# 13_-_USB.net
KiCad netlist of a schematic drawn in Altium Designer
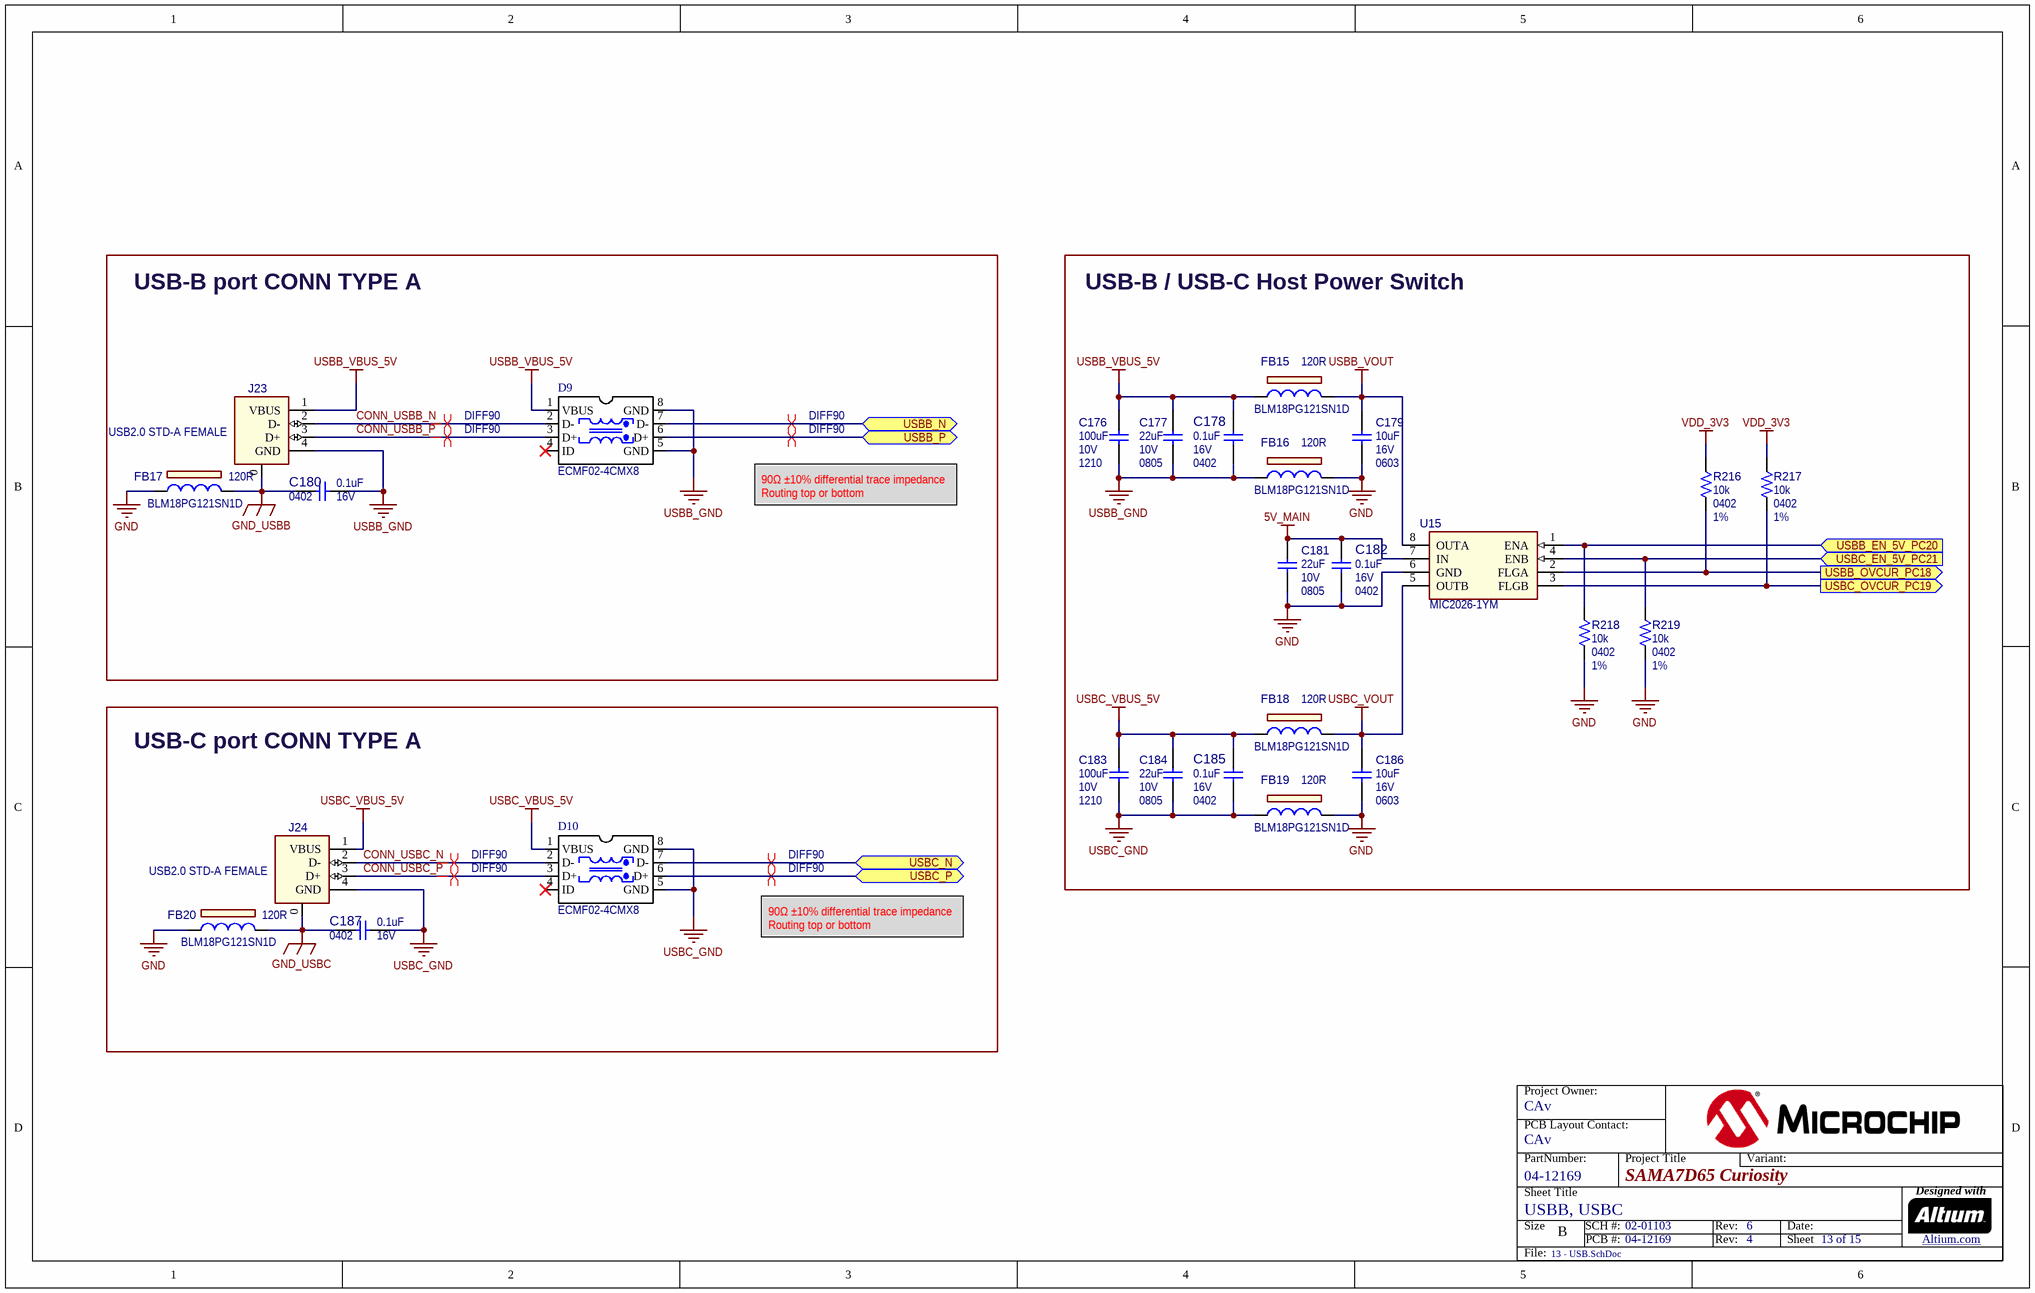
[diagram p0: 13 - USB.SchDoc]

(export (version "E")
  (design (tool "Eeschema 10.0.6"))
  (components
    (comp (ref "C176")
      (value "100uF")
      (footprint "CAP_C_1210")
      (description "Capacitor")
      (fields
        (field (name "VOLTAGE") "10V")
        (field (name "PACKAGE") "1210")
        (field (name "TOLERANCE") "20%")
        (field (name "Comment") "Capacitor NP")
      )
      (libsource (lib "") (part "Capacitor NP_1"))
    )
    (comp (ref "C177")
      (value "22uF")
      (footprint "CAP_C_0805")
      (fields
        (field (name "VOLTAGE") "10V")
        (field (name "PACKAGE") "0805")
        (field (name "TOLERANCE") "20%")
        (field (name "Comment") "Capacitor NP")
        (field (name "OWNER") "Razvan Cristescu")
      )
      (libsource (lib "MCHP-CDB") (part "Capacitor NP"))
    )
    (comp (ref "C178")
      (value "0.1uF")
      (footprint "CAP_C_0402")
      (fields
        (field (name "VOLTAGE") "16V")
        (field (name "PACKAGE") "0402")
        (field (name "TOLERANCE") "10%")
        (field (name "Comment") "Capacitor NP")
        (field (name "OWNER") "Sompoch Loboonlert")
      )
      (libsource (lib "MCHP-CDB") (part "Capacitor NP"))
    )
    (comp (ref "C179")
      (value "10uF")
      (footprint "CAP_C_0603")
      (fields
        (field (name "VOLTAGE") "16V")
        (field (name "PACKAGE") "0603")
        (field (name "TOLERANCE") "10%")
        (field (name "Comment") "Capacitor NP")
        (field (name "OWNER") "Sam Charles")
      )
      (libsource (lib "MCHP-CDB") (part "Capacitor NP"))
    )
    (comp (ref "C180")
      (value "0.1uF")
      (footprint "CAP_C_0402")
      (fields
        (field (name "VOLTAGE") "16V")
        (field (name "PACKAGE") "0402")
        (field (name "TOLERANCE") "10%")
        (field (name "Comment") "Capacitor NP")
        (field (name "OWNER") "Sompoch Loboonlert")
      )
      (libsource (lib "MCHP-CDB") (part "Capacitor NP"))
    )
    (comp (ref "C181")
      (value "22uF")
      (footprint "CAP_C_0805")
      (fields
        (field (name "VOLTAGE") "10V")
        (field (name "PACKAGE") "0805")
        (field (name "TOLERANCE") "20%")
        (field (name "Comment") "Capacitor NP")
        (field (name "OWNER") "Razvan Cristescu")
      )
      (libsource (lib "MCHP-CDB") (part "Capacitor NP"))
    )
    (comp (ref "C182")
      (value "0.1uF")
      (footprint "CAP_C_0402")
      (fields
        (field (name "VOLTAGE") "16V")
        (field (name "PACKAGE") "0402")
        (field (name "TOLERANCE") "10%")
        (field (name "Comment") "Capacitor NP")
        (field (name "OWNER") "Sompoch Loboonlert")
      )
      (libsource (lib "MCHP-CDB") (part "Capacitor NP"))
    )
    (comp (ref "C183")
      (value "100uF")
      (footprint "CAP_C_1210")
      (description "Capacitor")
      (fields
        (field (name "VOLTAGE") "10V")
        (field (name "PACKAGE") "1210")
        (field (name "TOLERANCE") "20%")
        (field (name "Comment") "Capacitor NP")
      )
      (libsource (lib "") (part "Capacitor NP_1"))
    )
    (comp (ref "C184")
      (value "22uF")
      (footprint "CAP_C_0805")
      (fields
        (field (name "VOLTAGE") "10V")
        (field (name "PACKAGE") "0805")
        (field (name "TOLERANCE") "20%")
        (field (name "Comment") "Capacitor NP")
        (field (name "OWNER") "Razvan Cristescu")
      )
      (libsource (lib "MCHP-CDB") (part "Capacitor NP"))
    )
    (comp (ref "C185")
      (value "0.1uF")
      (footprint "CAP_C_0402")
      (fields
        (field (name "VOLTAGE") "16V")
        (field (name "PACKAGE") "0402")
        (field (name "TOLERANCE") "10%")
        (field (name "Comment") "Capacitor NP")
        (field (name "OWNER") "Sompoch Loboonlert")
      )
      (libsource (lib "MCHP-CDB") (part "Capacitor NP"))
    )
    (comp (ref "C186")
      (value "10uF")
      (footprint "CAP_C_0603")
      (fields
        (field (name "VOLTAGE") "16V")
        (field (name "PACKAGE") "0603")
        (field (name "TOLERANCE") "10%")
        (field (name "Comment") "Capacitor NP")
        (field (name "OWNER") "Sam Charles")
      )
      (libsource (lib "MCHP-CDB") (part "Capacitor NP"))
    )
    (comp (ref "C187")
      (value "0.1uF")
      (footprint "CAP_C_0402")
      (fields
        (field (name "VOLTAGE") "16V")
        (field (name "PACKAGE") "0402")
        (field (name "TOLERANCE") "10%")
        (field (name "Comment") "Capacitor NP")
        (field (name "OWNER") "Sompoch Loboonlert")
      )
      (libsource (lib "MCHP-CDB") (part "Capacitor NP"))
    )
    (comp (ref "D9")
      (value "ECMF02-4CMX8")
      (footprint "DIODE ESD ECMF02-4CMX8")
      (description "IC ESD FILTER COMM MODE 8-UQFN")
      (fields (field (name "Comment") "ESD_ECMF02-4CMX8") (field (name "OWNER") "Dragos Danaila"))
      (libsource (lib "MCHP-CDB") (part "DIODE ESD ECMF02-4CMX8"))
    )
    (comp (ref "D10")
      (value "ECMF02-4CMX8")
      (footprint "DIODE ESD ECMF02-4CMX8")
      (description "IC ESD FILTER COMM MODE 8-UQFN")
      (fields (field (name "Comment") "ESD_ECMF02-4CMX8") (field (name "OWNER") "Dragos Danaila"))
      (libsource (lib "MCHP-CDB") (part "DIODE ESD ECMF02-4CMX8"))
    )
    (comp (ref "FB15")
      (value "120R")
      (footprint "IND_C_0603")
      (fields
        (field (name "MANUFACTURER PART NUMBER 1") "BLM18PG121SN1D")
        (field (name "Comment") "Ferrite Bead")
        (field (name "OWNER") "Petnarong Chaijaroong")
      )
      (libsource (lib "MCHP-CDB") (part "Ferrite Bead"))
    )
    (comp (ref "FB16")
      (value "120R")
      (footprint "IND_C_0603")
      (fields
        (field (name "MANUFACTURER PART NUMBER 1") "BLM18PG121SN1D")
        (field (name "Comment") "Ferrite Bead")
        (field (name "OWNER") "Petnarong Chaijaroong")
      )
      (libsource (lib "MCHP-CDB") (part "Ferrite Bead"))
    )
    (comp (ref "FB17")
      (value "120R")
      (footprint "IND_C_0603")
      (fields
        (field (name "MANUFACTURER PART NUMBER 1") "BLM18PG121SN1D")
        (field (name "Comment") "Ferrite Bead")
        (field (name "OWNER") "Petnarong Chaijaroong")
      )
      (libsource (lib "MCHP-CDB") (part "Ferrite Bead"))
    )
    (comp (ref "FB18")
      (value "120R")
      (footprint "IND_C_0603")
      (fields
        (field (name "MANUFACTURER PART NUMBER 1") "BLM18PG121SN1D")
        (field (name "Comment") "Ferrite Bead")
        (field (name "OWNER") "Petnarong Chaijaroong")
      )
      (libsource (lib "MCHP-CDB") (part "Ferrite Bead"))
    )
    (comp (ref "FB19")
      (value "120R")
      (footprint "IND_C_0603")
      (fields
        (field (name "MANUFACTURER PART NUMBER 1") "BLM18PG121SN1D")
        (field (name "Comment") "Ferrite Bead")
        (field (name "OWNER") "Petnarong Chaijaroong")
      )
      (libsource (lib "MCHP-CDB") (part "Ferrite Bead"))
    )
    (comp (ref "FB20")
      (value "120R")
      (footprint "IND_C_0603")
      (fields
        (field (name "MANUFACTURER PART NUMBER 1") "BLM18PG121SN1D")
        (field (name "Comment") "Ferrite Bead")
        (field (name "OWNER") "Petnarong Chaijaroong")
      )
      (libsource (lib "MCHP-CDB") (part "Ferrite Bead"))
    )
    (comp (ref "J23")
      (value "USB2.0 STD-A FEMALE")
      (footprint "CON_USB2.0-A_TH_RA_FCI_87520-0010BLF")
      (description "Connector USB")
      (fields (field (name "Comment") "CON USB2.0 A-B") (field (name "OWNER") "Bogdan Popescu"))
      (libsource (lib "MCHP-CDB") (part "CON USB2.0 A-B"))
    )
    (comp (ref "J24")
      (value "USB2.0 STD-A FEMALE")
      (footprint "CON_USB2.0-A_TH_RA_FCI_87520-0010BLF")
      (description "Connector USB")
      (fields (field (name "Comment") "CON USB2.0 A-B") (field (name "OWNER") "Bogdan Popescu"))
      (libsource (lib "MCHP-CDB") (part "CON USB2.0 A-B"))
    )
    (comp (ref "R216")
      (value "10k")
      (footprint "RES_C_0402")
      (description "Resistor")
      (fields
        (field (name "PACKAGE") "0402")
        (field (name "TOLERANCE") "1%")
        (field (name "VOLTAGE") "50V")
        (field (name "POWER") "1/10W")
        (field (name "OWNER") "Brent Lanphear")
      )
      (libsource (lib "MCHP-CDB") (part "Resistor"))
    )
    (comp (ref "R217")
      (value "10k")
      (footprint "RES_C_0402")
      (description "Resistor")
      (fields
        (field (name "PACKAGE") "0402")
        (field (name "TOLERANCE") "1%")
        (field (name "VOLTAGE") "50V")
        (field (name "POWER") "1/10W")
        (field (name "OWNER") "Brent Lanphear")
      )
      (libsource (lib "MCHP-CDB") (part "Resistor"))
    )
    (comp (ref "R218")
      (value "10k")
      (footprint "RES_C_0402")
      (description "Resistor")
      (fields
        (field (name "PACKAGE") "0402")
        (field (name "TOLERANCE") "1%")
        (field (name "VOLTAGE") "50V")
        (field (name "POWER") "1/10W")
        (field (name "OWNER") "Brent Lanphear")
      )
      (libsource (lib "MCHP-CDB") (part "Resistor"))
    )
    (comp (ref "R219")
      (value "10k")
      (footprint "RES_C_0402")
      (description "Resistor")
      (fields
        (field (name "PACKAGE") "0402")
        (field (name "TOLERANCE") "1%")
        (field (name "VOLTAGE") "50V")
        (field (name "POWER") "1/10W")
        (field (name "OWNER") "Brent Lanphear")
      )
      (libsource (lib "MCHP-CDB") (part "Resistor"))
    )
    (comp (ref "U15")
      (value "MIC2026-1YM")
      (footprint "SOIC-8")
      (fields (field (name "Comment") "MIC2026-2076 DIP-8 SOIC-8") (field (name "OWNER") "Sam Charles"))
      (libsource (lib "MCHP-CDB") (part "MIC2026-2076 DIP-8 SOIC-8"))
    )
  )
  (nets
    (net (code "1") (name "/CONN_USBB_N") (class "Default")
      (node (ref "D9") (pin "2") (pinfunction "D-_2") (pintype "passive"))
      (node (ref "J23") (pin "2") (pinfunction "D-_2") (pintype "bidirectional"))
    )
    (net (code "2") (name "/CONN_USBB_P") (class "Default")
      (node (ref "D9") (pin "3") (pinfunction "D+_3") (pintype "passive"))
      (node (ref "J23") (pin "3") (pinfunction "D+_3") (pintype "bidirectional"))
    )
    (net (code "3") (name "/CONN_USBC_N") (class "Default")
      (node (ref "D10") (pin "2") (pinfunction "D-_2") (pintype "passive"))
      (node (ref "J24") (pin "2") (pinfunction "D-_2") (pintype "bidirectional"))
    )
    (net (code "4") (name "/CONN_USBC_P") (class "Default")
      (node (ref "D10") (pin "3") (pinfunction "D+_3") (pintype "passive"))
      (node (ref "J24") (pin "3") (pinfunction "D+_3") (pintype "bidirectional"))
    )
    (net (code "5") (name "/USBB_EN_5V_PC20") (class "Default")
      (node (ref "R218") (pin "2") (pinfunction "2_2") (pintype "passive"))
      (node (ref "U15") (pin "1") (pinfunction "ENA_1") (pintype "input"))
    )
    (net (code "6") (name "/USBB_N") (class "Default")
      (node (ref "D9") (pin "7") (pinfunction "D-_7") (pintype "passive"))
    )
    (net (code "7") (name "/USBB_OVCUR_PC18") (class "Default")
      (node (ref "R216") (pin "1") (pinfunction "1_1") (pintype "passive"))
      (node (ref "U15") (pin "2") (pinfunction "FLGA_2") (pintype "open_collector"))
    )
    (net (code "8") (name "/USBB_P") (class "Default")
      (node (ref "D9") (pin "6") (pinfunction "D+_6") (pintype "passive"))
    )
    (net (code "9") (name "/USBC_EN_5V_PC21") (class "Default")
      (node (ref "R219") (pin "2") (pinfunction "2_2") (pintype "passive"))
      (node (ref "U15") (pin "4") (pinfunction "ENB_4") (pintype "input"))
    )
    (net (code "10") (name "/USBC_N") (class "Default")
      (node (ref "D10") (pin "7") (pinfunction "D-_7") (pintype "passive"))
    )
    (net (code "11") (name "/USBC_OVCUR_PC19") (class "Default")
      (node (ref "R217") (pin "1") (pinfunction "1_1") (pintype "passive"))
      (node (ref "U15") (pin "3") (pinfunction "FLGB_3") (pintype "open_collector"))
    )
    (net (code "12") (name "/USBC_P") (class "Default")
      (node (ref "D10") (pin "6") (pinfunction "D+_6") (pintype "passive"))
    )
    (net (code "13") (name "5V_MAIN") (class "Default")
      (node (ref "C181") (pin "1") (pinfunction "1_1") (pintype "passive"))
      (node (ref "C182") (pin "1") (pinfunction "1_1") (pintype "passive"))
      (node (ref "U15") (pin "7") (pinfunction "IN_7") (pintype "power_in"))
    )
    (net (code "14") (name "GND") (class "Default")
      (node (ref "C179") (pin "2") (pinfunction "2_2") (pintype "passive"))
      (node (ref "C181") (pin "2") (pinfunction "2_2") (pintype "passive"))
      (node (ref "C182") (pin "2") (pinfunction "2_2") (pintype "passive"))
      (node (ref "C186") (pin "2") (pinfunction "2_2") (pintype "passive"))
      (node (ref "FB16") (pin "2") (pinfunction "2_2") (pintype "passive"))
      (node (ref "FB17") (pin "1") (pinfunction "1_1") (pintype "passive"))
      (node (ref "FB19") (pin "2") (pinfunction "2_2") (pintype "passive"))
      (node (ref "FB20") (pin "1") (pinfunction "1_1") (pintype "passive"))
      (node (ref "R218") (pin "1") (pinfunction "1_1") (pintype "passive"))
      (node (ref "R219") (pin "1") (pinfunction "1_1") (pintype "passive"))
      (node (ref "U15") (pin "6") (pinfunction "GND_6") (pintype "power_in"))
    )
    (net (code "15") (name "GND_USBB") (class "Default")
      (node (ref "C180") (pin "1") (pinfunction "1_1") (pintype "passive"))
      (node (ref "FB17") (pin "2") (pinfunction "2_2") (pintype "passive"))
      (node (ref "J23") (pin "0") (pinfunction "SHLD_0") (pintype "passive"))
    )
    (net (code "16") (name "GND_USBC") (class "Default")
      (node (ref "C187") (pin "1") (pinfunction "1_1") (pintype "passive"))
      (node (ref "FB20") (pin "2") (pinfunction "2_2") (pintype "passive"))
      (node (ref "J24") (pin "0") (pinfunction "SHLD_0") (pintype "passive"))
    )
    (net (code "17") (name "USBB_GND") (class "Default")
      (node (ref "C176") (pin "2") (pinfunction "2_2") (pintype "passive"))
      (node (ref "C177") (pin "2") (pinfunction "2_2") (pintype "passive"))
      (node (ref "C178") (pin "2") (pinfunction "2_2") (pintype "passive"))
      (node (ref "C180") (pin "2") (pinfunction "2_2") (pintype "passive"))
      (node (ref "D9") (pin "5") (pinfunction "GND_5") (pintype "passive"))
      (node (ref "D9") (pin "8") (pinfunction "GND_8") (pintype "passive"))
      (node (ref "FB16") (pin "1") (pinfunction "1_1") (pintype "passive"))
      (node (ref "J23") (pin "4") (pinfunction "GND_4") (pintype "power_in"))
    )
    (net (code "18") (name "USBB_VBUS_5V") (class "Default")
      (node (ref "C176") (pin "1") (pinfunction "1_1") (pintype "passive"))
      (node (ref "C177") (pin "1") (pinfunction "1_1") (pintype "passive"))
      (node (ref "C178") (pin "1") (pinfunction "1_1") (pintype "passive"))
      (node (ref "D9") (pin "1") (pinfunction "VBUS_1") (pintype "passive"))
      (node (ref "FB15") (pin "1") (pinfunction "1_1") (pintype "passive"))
      (node (ref "J23") (pin "1") (pinfunction "VBUS_1") (pintype "power_in"))
    )
    (net (code "19") (name "USBB_VOUT") (class "Default")
      (node (ref "C179") (pin "1") (pinfunction "1_1") (pintype "passive"))
      (node (ref "FB15") (pin "2") (pinfunction "2_2") (pintype "passive"))
      (node (ref "U15") (pin "8") (pinfunction "OUTA_8") (pintype "power_in"))
    )
    (net (code "20") (name "USBC_GND") (class "Default")
      (node (ref "C183") (pin "2") (pinfunction "2_2") (pintype "passive"))
      (node (ref "C184") (pin "2") (pinfunction "2_2") (pintype "passive"))
      (node (ref "C185") (pin "2") (pinfunction "2_2") (pintype "passive"))
      (node (ref "C187") (pin "2") (pinfunction "2_2") (pintype "passive"))
      (node (ref "D10") (pin "5") (pinfunction "GND_5") (pintype "passive"))
      (node (ref "D10") (pin "8") (pinfunction "GND_8") (pintype "passive"))
      (node (ref "FB19") (pin "1") (pinfunction "1_1") (pintype "passive"))
      (node (ref "J24") (pin "4") (pinfunction "GND_4") (pintype "power_in"))
    )
    (net (code "21") (name "USBC_VBUS_5V") (class "Default")
      (node (ref "C183") (pin "1") (pinfunction "1_1") (pintype "passive"))
      (node (ref "C184") (pin "1") (pinfunction "1_1") (pintype "passive"))
      (node (ref "C185") (pin "1") (pinfunction "1_1") (pintype "passive"))
      (node (ref "D10") (pin "1") (pinfunction "VBUS_1") (pintype "passive"))
      (node (ref "FB18") (pin "1") (pinfunction "1_1") (pintype "passive"))
      (node (ref "J24") (pin "1") (pinfunction "VBUS_1") (pintype "power_in"))
    )
    (net (code "22") (name "USBC_VOUT") (class "Default")
      (node (ref "C186") (pin "1") (pinfunction "1_1") (pintype "passive"))
      (node (ref "FB18") (pin "2") (pinfunction "2_2") (pintype "passive"))
      (node (ref "U15") (pin "5") (pinfunction "OUTB_5") (pintype "power_in"))
    )
    (net (code "23") (name "VDD_3V3") (class "Default")
      (node (ref "R216") (pin "2") (pinfunction "2_2") (pintype "passive"))
      (node (ref "R217") (pin "2") (pinfunction "2_2") (pintype "passive"))
    )
    (net (code "24") (name "unconnected-(D9-ID-Pad4)") (class "Default")
      (node (ref "D9") (pin "4") (pinfunction "ID_4") (pintype "passive+no_connect"))
    )
    (net (code "25") (name "unconnected-(D10-ID-Pad4)") (class "Default")
      (node (ref "D10") (pin "4") (pinfunction "ID_4") (pintype "passive+no_connect"))
    )
  )
)
